# Convertisseur_SPI_RS232.net
KiCad netlist of a schematic drawn in Altium Designer
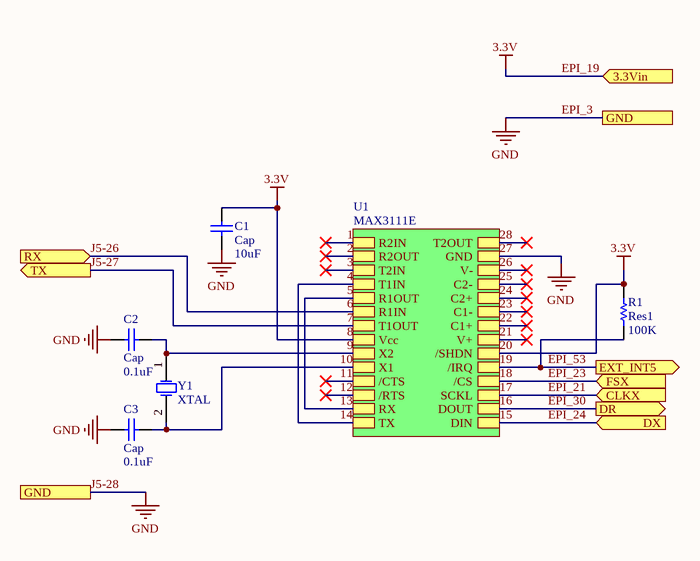
[diagram p0: Convertisseur_SPI_RS232.SchDoc]

(export (version "E")
  (design (tool "Eeschema 10.0.6"))
  (components
    (comp (ref "C1")
      (value "Cap")
      (footprint "RAD-0.3")
      (description "Capacitor")
      (fields (field (name "ALTIUM_VALUE") "10uF") (field (name "PUBLISHER") "Altium Limited"))
      (libsource (lib "Miscellaneous Devices") (part "Cap"))
    )
    (comp (ref "C2")
      (value "Cap")
      (footprint "RAD-0.3")
      (description "Capacitor")
      (fields (field (name "ALTIUM_VALUE") "0.1uF") (field (name "PUBLISHER") "Altium Limited"))
      (libsource (lib "Miscellaneous Devices") (part "Cap"))
    )
    (comp (ref "C3")
      (value "Cap")
      (footprint "RAD-0.3")
      (description "Capacitor")
      (fields (field (name "ALTIUM_VALUE") "0.1uF") (field (name "PUBLISHER") "Altium Limited"))
      (libsource (lib "Miscellaneous Devices") (part "Cap"))
    )
    (comp (ref "R1")
      (value "Res1")
      (footprint "AXIAL-0.3")
      (description "Resistor")
      (fields (field (name "ALTIUM_VALUE") "100K") (field (name "PUBLISHER") "Altium Limited"))
      (libsource (lib "Miscellaneous Devices") (part "Res1"))
    )
    (comp (ref "Y1")
      (value "XTAL")
      (footprint "R38")
      (description "Crystal Oscillator")
      (fields (field (name "PUBLISHER") "Altium Limited"))
      (libsource (lib "Miscellaneous Devices") (part "XTAL"))
    )
  )
  (nets
    (net (code "6") (name "/9") (class "Default")
      (node (ref "C2") (pin "2") (pinfunction "2_2") (pintype "passive"))
      (node (ref "Y1") (pin "1") (pinfunction "OSC1_1") (pintype "passive"))
    )
    (net (code "7") (name "/10") (class "Default")
      (node (ref "C3") (pin "2") (pinfunction "2_2") (pintype "passive"))
      (node (ref "Y1") (pin "2") (pinfunction "OSC2_2") (pintype "passive"))
    )
    (net (code "16") (name "/19") (class "Default")
      (node (ref "R1") (pin "2") (pinfunction "2_2") (pintype "passive"))
    )
    (net (code "24") (name "3.3V") (class "Default")
      (node (ref "C1") (pin "2") (pinfunction "2_2") (pintype "passive"))
      (node (ref "R1") (pin "1") (pinfunction "1_1") (pintype "passive"))
    )
    (net (code "25") (name "GND") (class "Default")
      (node (ref "C1") (pin "1") (pinfunction "1_1") (pintype "passive"))
      (node (ref "C2") (pin "1") (pinfunction "1_1") (pintype "passive"))
      (node (ref "C3") (pin "1") (pinfunction "1_1") (pintype "passive"))
    )
  )
)
